# sdr_3157.net
KiCad netlist of a schematic drawn in EAGLE
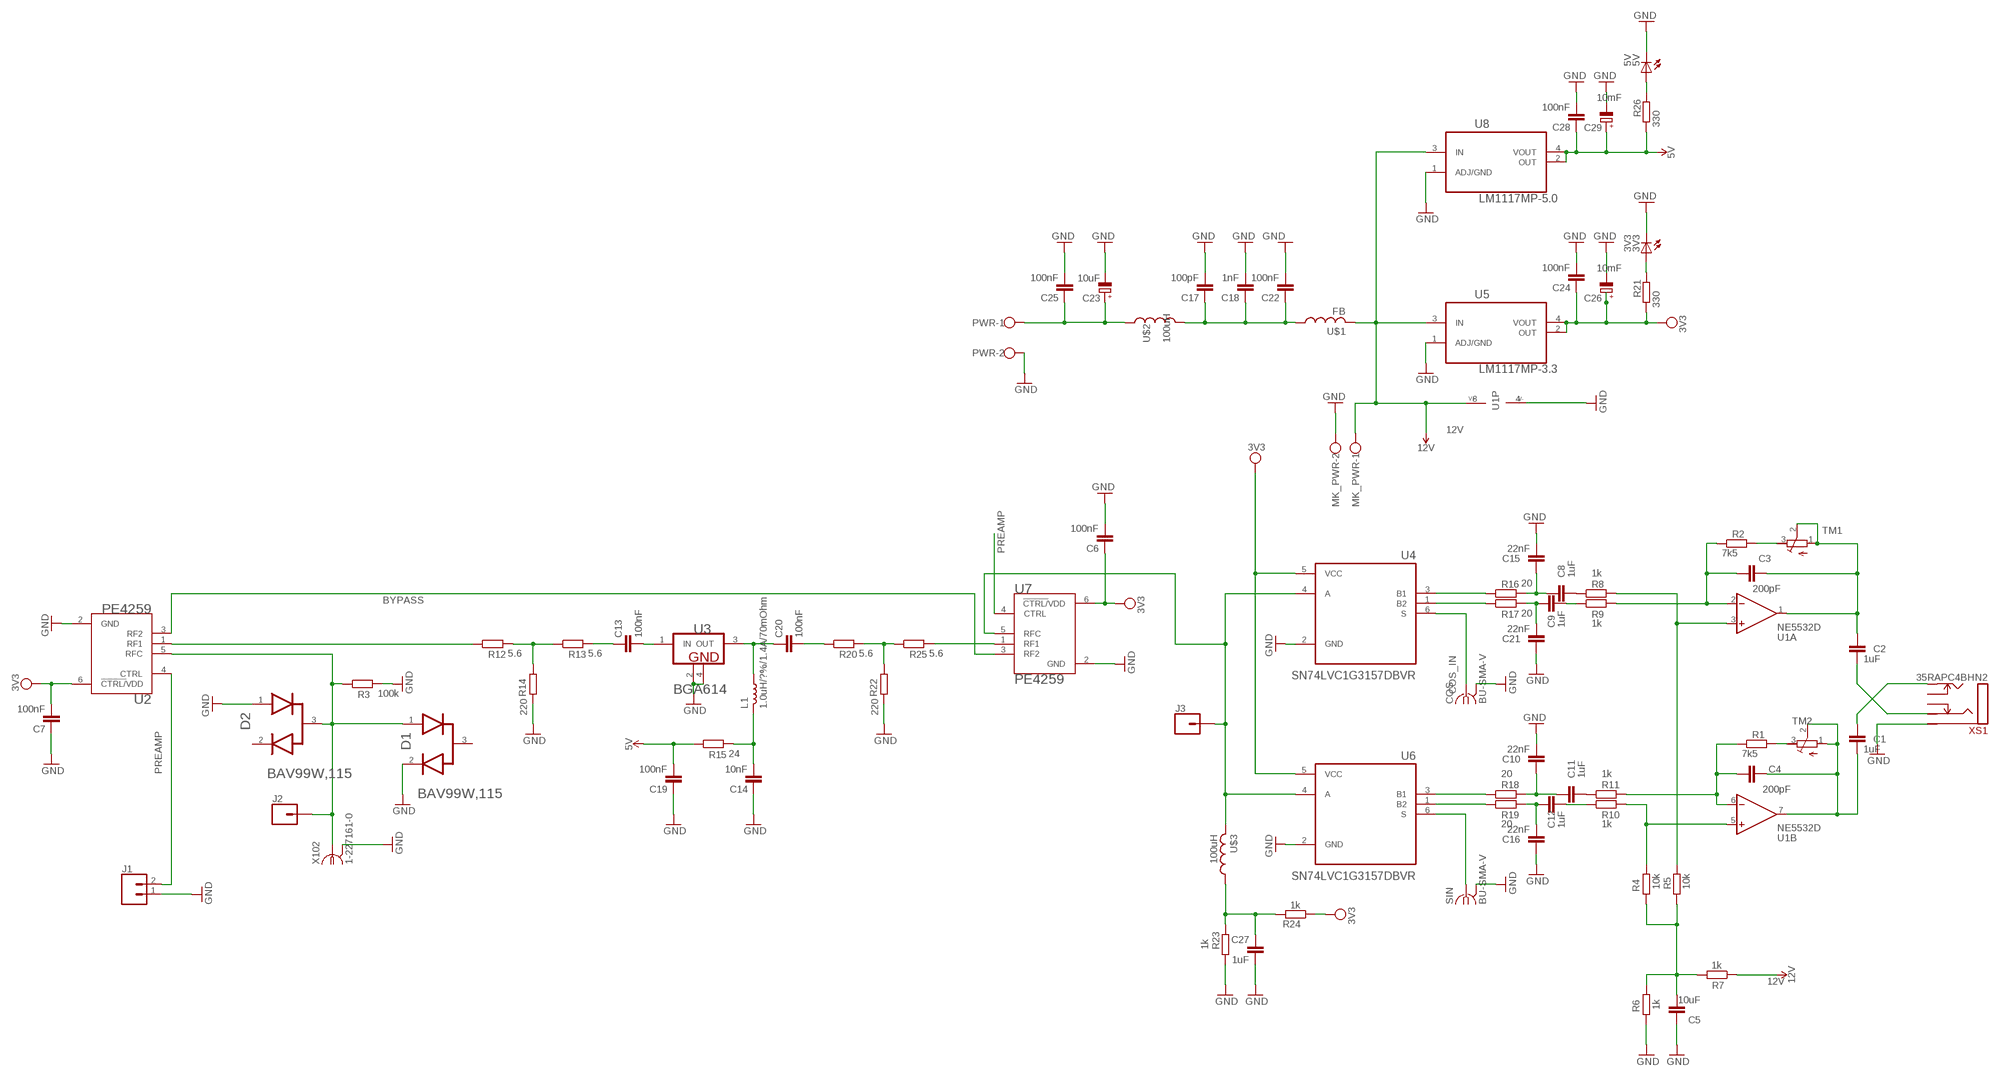
[diagram p0: schematic, sheet 1]

(export (version "E")
  (design (tool "Eeschema 10.0.6"))
  (components
    (comp (ref "3V3")
      (value "3V3")
      (footprint "eagle-import:1206")
      (libsource (lib "eagle-import") (part "LEDSMT1206"))
    )
    (comp (ref "5V")
      (value "5V")
      (footprint "eagle-import:1206")
      (libsource (lib "eagle-import") (part "LEDSMT1206"))
    )
    (comp (ref "C1")
      (value "1uF")
      (footprint "eagle-import:C050-045X075")
      (libsource (lib "eagle-import") (part "C-EU050-045X075"))
    )
    (comp (ref "C2")
      (value "1uF")
      (footprint "eagle-import:C050-045X075")
      (libsource (lib "eagle-import") (part "C-EU050-045X075"))
    )
    (comp (ref "C3")
      (value "200pF")
      (footprint "eagle-import:C050-045X075")
      (libsource (lib "eagle-import") (part "C-EU050-045X075"))
    )
    (comp (ref "C4")
      (value "200pF")
      (footprint "eagle-import:C050-045X075")
      (libsource (lib "eagle-import") (part "C-EU050-045X075"))
    )
    (comp (ref "C5")
      (value "10uF")
      (footprint "eagle-import:C0805")
      (libsource (lib "eagle-import") (part "C-EUC0805"))
    )
    (comp (ref "C6")
      (value "100nF")
      (footprint "eagle-import:C0805")
      (libsource (lib "eagle-import") (part "C-EUC0805"))
    )
    (comp (ref "C7")
      (value "100nF")
      (footprint "eagle-import:C0805")
      (libsource (lib "eagle-import") (part "C-EUC0805"))
    )
    (comp (ref "C8")
      (value "1uF")
      (footprint "eagle-import:C0805")
      (libsource (lib "eagle-import") (part "C-EUC0805"))
    )
    (comp (ref "C9")
      (value "1uF")
      (footprint "eagle-import:C0805")
      (libsource (lib "eagle-import") (part "C-EUC0805"))
    )
    (comp (ref "C10")
      (value "22nF")
      (footprint "eagle-import:C0805")
      (libsource (lib "eagle-import") (part "C-EUC0805"))
    )
    (comp (ref "C11")
      (value "1uF")
      (footprint "eagle-import:C0805")
      (libsource (lib "eagle-import") (part "C-EUC0805"))
    )
    (comp (ref "C12")
      (value "1uF")
      (footprint "eagle-import:C0805")
      (libsource (lib "eagle-import") (part "C-EUC0805"))
    )
    (comp (ref "C13")
      (value "100nF")
      (footprint "eagle-import:C0805")
      (libsource (lib "eagle-import") (part "C-EUC0805"))
    )
    (comp (ref "C14")
      (value "10nF")
      (footprint "eagle-import:C0805")
      (libsource (lib "eagle-import") (part "C-EUC0805"))
    )
    (comp (ref "C15")
      (value "22nF")
      (footprint "eagle-import:C0805")
      (libsource (lib "eagle-import") (part "C-EUC0805"))
    )
    (comp (ref "C16")
      (value "22nF")
      (footprint "eagle-import:C0805")
      (libsource (lib "eagle-import") (part "C-EUC0805"))
    )
    (comp (ref "C17")
      (value "100pF")
      (footprint "eagle-import:C0805")
      (libsource (lib "eagle-import") (part "C-EUC0805"))
    )
    (comp (ref "C18")
      (value "1nF")
      (footprint "eagle-import:C0805")
      (libsource (lib "eagle-import") (part "C-EUC0805"))
    )
    (comp (ref "C19")
      (value "100nF")
      (footprint "eagle-import:C0805")
      (libsource (lib "eagle-import") (part "C-EUC0805"))
    )
    (comp (ref "C20")
      (value "100nF")
      (footprint "eagle-import:C0805")
      (libsource (lib "eagle-import") (part "C-EUC0805"))
    )
    (comp (ref "C21")
      (value "22nF")
      (footprint "eagle-import:C0805")
      (libsource (lib "eagle-import") (part "C-EUC0805"))
    )
    (comp (ref "C22")
      (value "100nF")
      (footprint "eagle-import:C0805")
      (libsource (lib "eagle-import") (part "C-EUC0805"))
    )
    (comp (ref "C23")
      (value "10uF")
      (footprint "eagle-import:SMC_C")
      (libsource (lib "eagle-import") (part "CPOL-EUSMCC"))
    )
    (comp (ref "C24")
      (value "100nF")
      (footprint "eagle-import:C0805")
      (libsource (lib "eagle-import") (part "C-EUC0805"))
    )
    (comp (ref "C25")
      (value "100nF")
      (footprint "eagle-import:C0805")
      (libsource (lib "eagle-import") (part "C-EUC0805"))
    )
    (comp (ref "C26")
      (value "10mF")
      (footprint "eagle-import:SMC_C")
      (libsource (lib "eagle-import") (part "CPOL-EUSMCC"))
    )
    (comp (ref "C27")
      (value "1uF")
      (footprint "eagle-import:C0805")
      (libsource (lib "eagle-import") (part "C-EUC0805"))
    )
    (comp (ref "C28")
      (value "100nF")
      (footprint "eagle-import:C0805")
      (libsource (lib "eagle-import") (part "C-EUC0805"))
    )
    (comp (ref "C29")
      (value "10mF")
      (footprint "eagle-import:SMC_C")
      (libsource (lib "eagle-import") (part "CPOL-EUSMCC"))
    )
    (comp (ref "COS")
      (value "BU-SMA-V")
      (footprint "eagle-import:BU-SMA-V")
      (libsource (lib "eagle-import") (part "BU-SMA-V"))
    )
    (comp (ref "D1")
      (value "NEXPERIA_BAV99W,115NEXPERIA_BAV99W,115_0_0")
      (footprint "eagle-import:NEXPERIA_BAV99W,115_0")
      (fields
        (field (name "3DS_PART_NUMBER") "412-00001")
        (field (name "DIGIKEY_PART_NUMBER") "1727-2915-1-ND")
        (field (name "MF") "Nexperia")
      )
      (libsource (lib "eagle-import") (part "NEXPERIA_BAV99W,115NEXPERIA_BAV99W,115_0_0"))
    )
    (comp (ref "D2")
      (value "NEXPERIA_BAV99W,115NEXPERIA_BAV99W,115_0_0")
      (footprint "eagle-import:NEXPERIA_BAV99W,115_0")
      (fields
        (field (name "3DS_PART_NUMBER") "412-00001")
        (field (name "DIGIKEY_PART_NUMBER") "1727-2915-1-ND")
        (field (name "MF") "Nexperia")
      )
      (libsource (lib "eagle-import") (part "NEXPERIA_BAV99W,115NEXPERIA_BAV99W,115_0_0"))
    )
    (comp (ref "J1")
      (value "CONN_02")
      (footprint "eagle-import:1X02")
      (libsource (lib "eagle-import") (part "CONN_02"))
    )
    (comp (ref "J2")
      (value "CONN_01PTH_NO_SILK_SMALL")
      (footprint "eagle-import:1X01_SMALL")
      (libsource (lib "eagle-import") (part "CONN_01PTH_NO_SILK_SMALL"))
    )
    (comp (ref "J3")
      (value "CONN_01PTH_NO_SILK_SMALL")
      (footprint "eagle-import:1X01_SMALL")
      (libsource (lib "eagle-import") (part "CONN_01PTH_NO_SILK_SMALL"))
    )
    (comp (ref "L1")
      (value "1.0uH/?%/1.4A/70mOhm")
      (footprint "eagle-import:0805-WIDE")
      (libsource (lib "eagle-import") (part "INDUCTOR-0805_WIDE-1.0UH"))
    )
    (comp (ref "MK_PWR")
      (value "W237-102")
      (footprint "eagle-import:W237-102")
      (fields (field (name "MPN") "237-102"))
      (libsource (lib "eagle-import") (part "W237-102"))
    )
    (comp (ref "PWR")
      (value "W237-102")
      (footprint "eagle-import:W237-102")
      (fields (field (name "MPN") "237-102"))
      (libsource (lib "eagle-import") (part "W237-102"))
    )
    (comp (ref "R1")
      (value "7k5")
      (footprint "eagle-import:R0805")
      (libsource (lib "eagle-import") (part "R-EU_R0805"))
    )
    (comp (ref "R2")
      (value "7k5")
      (footprint "eagle-import:R0805")
      (libsource (lib "eagle-import") (part "R-EU_R0805"))
    )
    (comp (ref "R3")
      (value "100k")
      (footprint "eagle-import:R0805")
      (libsource (lib "eagle-import") (part "R-EU_R0805"))
    )
    (comp (ref "R4")
      (value "10k")
      (footprint "eagle-import:M0805")
      (libsource (lib "eagle-import") (part "R-EU_M0805"))
    )
    (comp (ref "R5")
      (value "10k")
      (footprint "eagle-import:R0805")
      (libsource (lib "eagle-import") (part "R-EU_R0805"))
    )
    (comp (ref "R6")
      (value "1k")
      (footprint "eagle-import:M0805")
      (libsource (lib "eagle-import") (part "R-EU_M0805"))
    )
    (comp (ref "R7")
      (value "1k")
      (footprint "eagle-import:M0805")
      (libsource (lib "eagle-import") (part "R-EU_M0805"))
    )
    (comp (ref "R8")
      (value "1k")
      (footprint "eagle-import:R0805")
      (libsource (lib "eagle-import") (part "R-EU_R0805"))
    )
    (comp (ref "R9")
      (value "1k")
      (footprint "eagle-import:R0805")
      (libsource (lib "eagle-import") (part "R-EU_R0805"))
    )
    (comp (ref "R10")
      (value "1k")
      (footprint "eagle-import:R0805")
      (libsource (lib "eagle-import") (part "R-EU_R0805"))
    )
    (comp (ref "R11")
      (value "1k")
      (footprint "eagle-import:M0805")
      (libsource (lib "eagle-import") (part "R-EU_M0805"))
    )
    (comp (ref "R12")
      (value "5.6")
      (footprint "eagle-import:R0805")
      (libsource (lib "eagle-import") (part "R-EU_R0805"))
    )
    (comp (ref "R13")
      (value "5.6")
      (footprint "eagle-import:R0805")
      (libsource (lib "eagle-import") (part "R-EU_R0805"))
    )
    (comp (ref "R14")
      (value "220")
      (footprint "eagle-import:R0805")
      (libsource (lib "eagle-import") (part "R-EU_R0805"))
    )
    (comp (ref "R15")
      (value "24")
      (footprint "eagle-import:R0805")
      (libsource (lib "eagle-import") (part "R-EU_R0805"))
    )
    (comp (ref "R16")
      (value "20")
      (footprint "eagle-import:R0805")
      (libsource (lib "eagle-import") (part "R-EU_R0805"))
    )
    (comp (ref "R17")
      (value "20")
      (footprint "eagle-import:R0805")
      (libsource (lib "eagle-import") (part "R-EU_R0805"))
    )
    (comp (ref "R18")
      (value "20")
      (footprint "eagle-import:R0805")
      (libsource (lib "eagle-import") (part "R-EU_R0805"))
    )
    (comp (ref "R19")
      (value "20")
      (footprint "eagle-import:R0805")
      (libsource (lib "eagle-import") (part "R-EU_R0805"))
    )
    (comp (ref "R20")
      (value "5.6")
      (footprint "eagle-import:R0805")
      (libsource (lib "eagle-import") (part "R-EU_R0805"))
    )
    (comp (ref "R21")
      (value "330")
      (footprint "eagle-import:R0805")
      (libsource (lib "eagle-import") (part "R-EU_R0805"))
    )
    (comp (ref "R22")
      (value "220")
      (footprint "eagle-import:R0805")
      (libsource (lib "eagle-import") (part "R-EU_R0805"))
    )
    (comp (ref "R23")
      (value "1k")
      (footprint "eagle-import:R0805")
      (libsource (lib "eagle-import") (part "R-EU_R0805"))
    )
    (comp (ref "R24")
      (value "1k")
      (footprint "eagle-import:R0805")
      (libsource (lib "eagle-import") (part "R-EU_R0805"))
    )
    (comp (ref "R25")
      (value "5.6")
      (footprint "eagle-import:R0805")
      (libsource (lib "eagle-import") (part "R-EU_R0805"))
    )
    (comp (ref "R26")
      (value "330")
      (footprint "eagle-import:R0805")
      (libsource (lib "eagle-import") (part "R-EU_R0805"))
    )
    (comp (ref "SIN")
      (value "BU-SMA-V")
      (footprint "eagle-import:BU-SMA-V")
      (libsource (lib "eagle-import") (part "BU-SMA-V"))
    )
    (comp (ref "TM1")
      (value "5k")
      (footprint "eagle-import:RTRIM3296W")
      (libsource (lib "eagle-import") (part "R-TRIMM3296W"))
    )
    (comp (ref "TM2")
      (value "5k")
      (footprint "eagle-import:RTRIM3296W")
      (libsource (lib "eagle-import") (part "R-TRIMM3296W"))
    )
    (comp (ref "U$1") (value "FB") (footprint "eagle-import:FB") (libsource (lib "eagle-import") (part "FB")))
    (comp (ref "U$2")
      (value "100uH")
      (footprint "eagle-import:IHLP4040")
      (libsource (lib "eagle-import") (part "IHLP4040"))
    )
    (comp (ref "U$3")
      (value "100uH")
      (footprint "eagle-import:LQH55")
      (libsource (lib "eagle-import") (part "L-LQH55"))
    )
    (comp (ref "U1")
      (value "NE5532D")
      (footprint "eagle-import:SO08")
      (libsource (lib "eagle-import") (part "NE5532D"))
    )
    (comp (ref "U2")
      (value "PE4259")
      (footprint "eagle-import:SOT65P215X110-6N")
      (fields (field (name "MF") "pSemi"))
      (libsource (lib "eagle-import") (part "PE4259"))
    )
    (comp (ref "U3")
      (value "INFINEON_BGA614INFINEON_BGA614_0_0")
      (footprint "eagle-import:INFINEON_BGA614_0")
      (fields (field (name "MF") "Infineon") (field (name "MPN") "BGA614"))
      (libsource (lib "eagle-import") (part "INFINEON_BGA614INFINEON_BGA614_0_0"))
    )
    (comp (ref "U4")
      (value "SN74LVC1G3157DBVR")
      (footprint "eagle-import:SOT95P280X145-6N")
      (fields (field (name "MF") "Texas Instruments"))
      (libsource (lib "eagle-import") (part "SN74LVC1G3157DBVR"))
    )
    (comp (ref "U5")
      (value "LM1117MP-3.3")
      (footprint "eagle-import:SOT230P696X180-4N")
      (fields (field (name "MF") "Texas Instruments"))
      (libsource (lib "eagle-import") (part "LM1117MP-3.3"))
    )
    (comp (ref "U6")
      (value "SN74LVC1G3157DBVR")
      (footprint "eagle-import:SOT95P280X145-6N")
      (fields (field (name "MF") "Texas Instruments"))
      (libsource (lib "eagle-import") (part "SN74LVC1G3157DBVR"))
    )
    (comp (ref "U7")
      (value "PE4259")
      (footprint "eagle-import:SOT65P215X110-6N")
      (fields (field (name "MF") "pSemi"))
      (libsource (lib "eagle-import") (part "PE4259"))
    )
    (comp (ref "U8")
      (value "LM1117MP-5.0")
      (footprint "eagle-import:SOT230P696X180-4N")
      (fields (field (name "MF") "Texas Instruments") (field (name "MP") "LM1117MP-3.3"))
      (libsource (lib "eagle-import") (part "LM1117MP-3.3"))
    )
    (comp (ref "X102")
      (value "1-227161-0")
      (footprint "eagle-import:AMP_227161")
      (fields (field (name "MF") "TYCO ELECTRONICS") (field (name "MPN") "1-227161"))
      (libsource (lib "eagle-import") (part "?2271611--0"))
    )
    (comp (ref "XS1")
      (value "35RAPC4BHN2")
      (footprint "eagle-import:35RAP")
      (libsource (lib "eagle-import") (part "35RAPC4BHN2"))
    )
  )
  (nets
    (net (code "1") (name "/BYPASS") (class "Default")
      (node (ref "U2") (pin "3") (pinfunction "RF2_3") (pintype "passive"))
      (node (ref "U7") (pin "3") (pinfunction "RF2_3") (pintype "passive"))
    )
    (net (code "2") (name "/COS_IN") (class "Default")
      (node (ref "COS") (pin "1") (pinfunction "1_1") (pintype "passive"))
      (node (ref "U4") (pin "6") (pinfunction "S_6") (pintype "input"))
    )
    (net (code "3") (name "/PREAMP") (class "Default")
      (node (ref "J1") (pin "2") (pinfunction "2_2") (pintype "passive"))
      (node (ref "U2") (pin "4") (pinfunction "CTRL_4") (pintype "input"))
      (node (ref "U7") (pin "4") (pinfunction "CTRL_4") (pintype "input"))
    )
    (net (code "4") (name "3V3") (class "Default")
      (node (ref "C24") (pin "1") (pinfunction "1_1") (pintype "passive"))
      (node (ref "C26") (pin "+") (pinfunction "+_+") (pintype "passive"))
      (node (ref "C6") (pin "1") (pinfunction "1_1") (pintype "passive"))
      (node (ref "C7") (pin "2") (pinfunction "2_2") (pintype "passive"))
      (node (ref "R21") (pin "1") (pinfunction "1_1") (pintype "passive"))
      (node (ref "R24") (pin "1") (pinfunction "1_1") (pintype "passive"))
      (node (ref "U2") (pin "6") (pinfunction "~{CTRL/}VDD_6") (pintype "power_in"))
      (node (ref "U4") (pin "5") (pinfunction "VCC_5") (pintype "power_in"))
      (node (ref "U5") (pin "2") (pinfunction "OUT_2") (pintype "output"))
      (node (ref "U5") (pin "4") (pinfunction "VOUT_4") (pintype "output"))
      (node (ref "U6") (pin "5") (pinfunction "VCC_5") (pintype "power_in"))
      (node (ref "U7") (pin "6") (pinfunction "~{CTRL/}VDD_6") (pintype "power_in"))
    )
    (net (code "5") (name "5V") (class "Default")
      (node (ref "C19") (pin "2") (pinfunction "2_2") (pintype "passive"))
      (node (ref "C28") (pin "1") (pinfunction "1_1") (pintype "passive"))
      (node (ref "C29") (pin "+") (pinfunction "+_+") (pintype "passive"))
      (node (ref "R15") (pin "1") (pinfunction "1_1") (pintype "passive"))
      (node (ref "R26") (pin "1") (pinfunction "1_1") (pintype "passive"))
      (node (ref "U8") (pin "2") (pinfunction "OUT_2") (pintype "output"))
      (node (ref "U8") (pin "4") (pinfunction "VOUT_4") (pintype "output"))
    )
    (net (code "6") (name "12V") (class "Default")
      (node (ref "MK_PWR") (pin "1") (pinfunction "KL_1") (pintype "passive"))
      (node (ref "R7") (pin "1") (pinfunction "1_1") (pintype "passive"))
      (node (ref "U$1") (pin "P$2") (pinfunction "2_P$2") (pintype "passive"))
      (node (ref "U1") (pin "8") (pinfunction "V+_8") (pintype "power_in"))
      (node (ref "U5") (pin "3") (pinfunction "IN_3") (pintype "input"))
      (node (ref "U8") (pin "3") (pinfunction "IN_3") (pintype "input"))
    )
    (net (code "7") (name "GND") (class "Default")
      (node (ref "3V3") (pin "C") (pinfunction "C_C") (pintype "passive"))
      (node (ref "5V") (pin "C") (pinfunction "C_C") (pintype "passive"))
      (node (ref "C10") (pin "2") (pinfunction "2_2") (pintype "passive"))
      (node (ref "C14") (pin "1") (pinfunction "1_1") (pintype "passive"))
      (node (ref "C15") (pin "2") (pinfunction "2_2") (pintype "passive"))
      (node (ref "C16") (pin "1") (pinfunction "1_1") (pintype "passive"))
      (node (ref "C17") (pin "2") (pinfunction "2_2") (pintype "passive"))
      (node (ref "C18") (pin "2") (pinfunction "2_2") (pintype "passive"))
      (node (ref "C19") (pin "1") (pinfunction "1_1") (pintype "passive"))
      (node (ref "C21") (pin "1") (pinfunction "1_1") (pintype "passive"))
      (node (ref "C22") (pin "2") (pinfunction "2_2") (pintype "passive"))
      (node (ref "C23") (pin "-") (pinfunction "-_-") (pintype "passive"))
      (node (ref "C24") (pin "2") (pinfunction "2_2") (pintype "passive"))
      (node (ref "C25") (pin "2") (pinfunction "2_2") (pintype "passive"))
      (node (ref "C26") (pin "-") (pinfunction "-_-") (pintype "passive"))
      (node (ref "C27") (pin "1") (pinfunction "1_1") (pintype "passive"))
      (node (ref "C28") (pin "2") (pinfunction "2_2") (pintype "passive"))
      (node (ref "C29") (pin "-") (pinfunction "-_-") (pintype "passive"))
      (node (ref "C5") (pin "1") (pinfunction "1_1") (pintype "passive"))
      (node (ref "C6") (pin "2") (pinfunction "2_2") (pintype "passive"))
      (node (ref "C7") (pin "1") (pinfunction "1_1") (pintype "passive"))
      (node (ref "COS") (pin "2") (pinfunction "2_2") (pintype "passive"))
      (node (ref "COS") (pin "3") (pinfunction "2_3") (pintype "passive"))
      (node (ref "COS") (pin "4") (pinfunction "2_4") (pintype "passive"))
      (node (ref "COS") (pin "5") (pinfunction "2_5") (pintype "passive"))
      (node (ref "D1") (pin "2") (pinfunction "2_CATHODE_2") (pintype "passive"))
      (node (ref "D2") (pin "1") (pinfunction "1_ANODE_1") (pintype "passive"))
      (node (ref "J1") (pin "1") (pinfunction "1_1") (pintype "passive"))
      (node (ref "MK_PWR") (pin "2") (pinfunction "KL_2") (pintype "passive"))
      (node (ref "PWR") (pin "2") (pinfunction "KL_2") (pintype "passive"))
      (node (ref "R14") (pin "2") (pinfunction "2_2") (pintype "passive"))
      (node (ref "R22") (pin "2") (pinfunction "2_2") (pintype "passive"))
      (node (ref "R23") (pin "1") (pinfunction "1_1") (pintype "passive"))
      (node (ref "R3") (pin "2") (pinfunction "2_2") (pintype "passive"))
      (node (ref "R6") (pin "1") (pinfunction "1_1") (pintype "passive"))
      (node (ref "SIN") (pin "2") (pinfunction "2_2") (pintype "passive"))
      (node (ref "SIN") (pin "3") (pinfunction "2_3") (pintype "passive"))
      (node (ref "SIN") (pin "4") (pinfunction "2_4") (pintype "passive"))
      (node (ref "SIN") (pin "5") (pinfunction "2_5") (pintype "passive"))
      (node (ref "U1") (pin "4") (pinfunction "V-_4") (pintype "power_in"))
      (node (ref "U2") (pin "2") (pinfunction "GND_2") (pintype "power_in"))
      (node (ref "U3") (pin "2") (pinfunction "1_GND_2") (pintype "power_in"))
      (node (ref "U3") (pin "4") (pinfunction "2_GND_4") (pintype "power_in"))
      (node (ref "U4") (pin "2") (pinfunction "GND_2") (pintype "power_in"))
      (node (ref "U5") (pin "1") (pinfunction "ADJ/GND_1") (pintype "passive"))
      (node (ref "U6") (pin "2") (pinfunction "GND_2") (pintype "power_in"))
      (node (ref "U7") (pin "2") (pinfunction "GND_2") (pintype "power_in"))
      (node (ref "U8") (pin "1") (pinfunction "ADJ/GND_1") (pintype "passive"))
      (node (ref "X102") (pin "2") (pinfunction "2_2") (pintype "passive"))
      (node (ref "XS1") (pin "1") (pinfunction "S_1") (pintype "passive"))
    )
    (net (code "8") (name "Net-(3V3-PadA)") (class "Default")
      (node (ref "3V3") (pin "A") (pinfunction "A_A") (pintype "passive"))
      (node (ref "R21") (pin "2") (pinfunction "2_2") (pintype "passive"))
    )
    (net (code "9") (name "Net-(5V-PadA)") (class "Default")
      (node (ref "5V") (pin "A") (pinfunction "A_A") (pintype "passive"))
      (node (ref "R26") (pin "2") (pinfunction "2_2") (pintype "passive"))
    )
    (net (code "10") (name "Net-(C5-Pad2)") (class "Default")
      (node (ref "C5") (pin "2") (pinfunction "2_2") (pintype "passive"))
      (node (ref "R4") (pin "1") (pinfunction "1_1") (pintype "passive"))
      (node (ref "R5") (pin "1") (pinfunction "1_1") (pintype "passive"))
      (node (ref "R6") (pin "2") (pinfunction "2_2") (pintype "passive"))
      (node (ref "R7") (pin "2") (pinfunction "2_2") (pintype "passive"))
    )
    (net (code "11") (name "Net-(C8-Pad2)") (class "Default")
      (node (ref "C8") (pin "2") (pinfunction "2_2") (pintype "passive"))
      (node (ref "R8") (pin "1") (pinfunction "1_1") (pintype "passive"))
    )
    (net (code "12") (name "Net-(C9-Pad2)") (class "Default")
      (node (ref "C9") (pin "2") (pinfunction "2_2") (pintype "passive"))
      (node (ref "R9") (pin "1") (pinfunction "1_1") (pintype "passive"))
    )
    (net (code "13") (name "Net-(C10-Pad1)") (class "Default")
      (node (ref "C10") (pin "1") (pinfunction "1_1") (pintype "passive"))
      (node (ref "C11") (pin "1") (pinfunction "1_1") (pintype "passive"))
      (node (ref "R18") (pin "2") (pinfunction "2_2") (pintype "passive"))
    )
    (net (code "14") (name "Net-(C11-Pad2)") (class "Default")
      (node (ref "C11") (pin "2") (pinfunction "2_2") (pintype "passive"))
      (node (ref "R11") (pin "1") (pinfunction "1_1") (pintype "passive"))
    )
    (net (code "15") (name "Net-(C12-Pad1)") (class "Default")
      (node (ref "C12") (pin "1") (pinfunction "1_1") (pintype "passive"))
      (node (ref "C16") (pin "2") (pinfunction "2_2") (pintype "passive"))
      (node (ref "R19") (pin "2") (pinfunction "2_2") (pintype "passive"))
    )
    (net (code "16") (name "Net-(C12-Pad2)") (class "Default")
      (node (ref "C12") (pin "2") (pinfunction "2_2") (pintype "passive"))
      (node (ref "R10") (pin "1") (pinfunction "1_1") (pintype "passive"))
    )
    (net (code "17") (name "Net-(C13-Pad1)") (class "Default")
      (node (ref "C13") (pin "1") (pinfunction "1_1") (pintype "passive"))
      (node (ref "R13") (pin "2") (pinfunction "2_2") (pintype "passive"))
    )
    (net (code "18") (name "Net-(C14-Pad2)") (class "Default")
      (node (ref "C14") (pin "2") (pinfunction "2_2") (pintype "passive"))
      (node (ref "L1") (pin "2") (pinfunction "2_2") (pintype "passive"))
      (node (ref "R15") (pin "2") (pinfunction "2_2") (pintype "passive"))
    )
    (net (code "19") (name "Net-(C15-Pad1)") (class "Default")
      (node (ref "C15") (pin "1") (pinfunction "1_1") (pintype "passive"))
      (node (ref "C8") (pin "1") (pinfunction "1_1") (pintype "passive"))
      (node (ref "R16") (pin "2") (pinfunction "2_2") (pintype "passive"))
    )
    (net (code "20") (name "Net-(C20-Pad2)") (class "Default")
      (node (ref "C20") (pin "2") (pinfunction "2_2") (pintype "passive"))
      (node (ref "R20") (pin "1") (pinfunction "1_1") (pintype "passive"))
    )
    (net (code "21") (name "Net-(C21-Pad2)") (class "Default")
      (node (ref "C21") (pin "2") (pinfunction "2_2") (pintype "passive"))
      (node (ref "C9") (pin "1") (pinfunction "1_1") (pintype "passive"))
      (node (ref "R17") (pin "2") (pinfunction "2_2") (pintype "passive"))
    )
    (net (code "22") (name "Net-(C27-Pad2)") (class "Default")
      (node (ref "C27") (pin "2") (pinfunction "2_2") (pintype "passive"))
      (node (ref "R23") (pin "2") (pinfunction "2_2") (pintype "passive"))
      (node (ref "R24") (pin "2") (pinfunction "2_2") (pintype "passive"))
      (node (ref "U$3") (pin "1") (pinfunction "1_1") (pintype "passive"))
    )
    (net (code "23") (name "Net-(D1-1_ANODE)") (class "Default")
      (node (ref "D1") (pin "1") (pinfunction "1_ANODE_1") (pintype "passive"))
      (node (ref "D2") (pin "3") (pinfunction "1_CATHODE/2_ANODE_3") (pintype "passive"))
      (node (ref "J2") (pin "P$1") (pinfunction "1_P$1") (pintype "passive"))
      (node (ref "R3") (pin "1") (pinfunction "1_1") (pintype "passive"))
      (node (ref "U2") (pin "5") (pinfunction "RFC_5") (pintype "passive"))
      (node (ref "X102") (pin "1") (pinfunction "1_1") (pintype "passive"))
    )
    (net (code "24") (name "Net-(J3-1)") (class "Default")
      (node (ref "J3") (pin "P$1") (pinfunction "1_P$1") (pintype "passive"))
      (node (ref "U$3") (pin "2") (pinfunction "2_2") (pintype "passive"))
      (node (ref "U4") (pin "4") (pinfunction "A_4") (pintype "output"))
      (node (ref "U6") (pin "4") (pinfunction "A_4") (pintype "output"))
      (node (ref "U7") (pin "5") (pinfunction "RFC_5") (pintype "passive"))
    )
    (net (code "25") (name "Net-(PWRA-KL)") (class "Default")
      (node (ref "C23") (pin "+") (pinfunction "+_+") (pintype "passive"))
      (node (ref "C25") (pin "1") (pinfunction "1_1") (pintype "passive"))
      (node (ref "PWR") (pin "1") (pinfunction "KL_1") (pintype "passive"))
      (node (ref "U$2") (pin "1") (pinfunction "1_1") (pintype "passive"))
    )
    (net (code "26") (name "Net-(R12-Pad2)") (class "Default")
      (node (ref "R12") (pin "2") (pinfunction "2_2") (pintype "passive"))
      (node (ref "R13") (pin "1") (pinfunction "1_1") (pintype "passive"))
      (node (ref "R14") (pin "1") (pinfunction "1_1") (pintype "passive"))
    )
    (net (code "27") (name "Net-(R20-Pad2)") (class "Default")
      (node (ref "R20") (pin "2") (pinfunction "2_2") (pintype "passive"))
      (node (ref "R22") (pin "1") (pinfunction "1_1") (pintype "passive"))
      (node (ref "R25") (pin "1") (pinfunction "1_1") (pintype "passive"))
    )
    (net (code "28") (name "Net-(TM1-A)") (class "Default")
      (node (ref "C2") (pin "1") (pinfunction "1_1") (pintype "passive"))
      (node (ref "C3") (pin "2") (pinfunction "2_2") (pintype "passive"))
      (node (ref "TM1") (pin "1") (pinfunction "A_1") (pintype "passive"))
      (node (ref "TM1") (pin "2") (pinfunction "S_2") (pintype "passive"))
      (node (ref "U1") (pin "1") (pinfunction "OUT_1") (pintype "output"))
    )
    (net (code "29") (name "Net-(TM1-E)") (class "Default")
      (node (ref "R2") (pin "2") (pinfunction "2_2") (pintype "passive"))
      (node (ref "TM1") (pin "3") (pinfunction "E_3") (pintype "passive"))
    )
    (net (code "30") (name "Net-(TM2-A)") (class "Default")
      (node (ref "C1") (pin "2") (pinfunction "2_2") (pintype "passive"))
      (node (ref "C4") (pin "2") (pinfunction "2_2") (pintype "passive"))
      (node (ref "TM2") (pin "1") (pinfunction "A_1") (pintype "passive"))
      (node (ref "TM2") (pin "2") (pinfunction "S_2") (pintype "passive"))
      (node (ref "U1") (pin "7") (pinfunction "OUT_7") (pintype "output"))
    )
    (net (code "31") (name "Net-(TM2-E)") (class "Default")
      (node (ref "R1") (pin "2") (pinfunction "2_2") (pintype "passive"))
      (node (ref "TM2") (pin "3") (pinfunction "E_3") (pintype "passive"))
    )
    (net (code "32") (name "Net-(U$1-1)") (class "Default")
      (node (ref "C17") (pin "1") (pinfunction "1_1") (pintype "passive"))
      (node (ref "C18") (pin "1") (pinfunction "1_1") (pintype "passive"))
      (node (ref "C22") (pin "1") (pinfunction "1_1") (pintype "passive"))
      (node (ref "U$1") (pin "P$1") (pinfunction "1_P$1") (pintype "passive"))
      (node (ref "U$2") (pin "2") (pinfunction "2_2") (pintype "passive"))
    )
    (net (code "33") (name "Net-(U1A-+IN)") (class "Default")
      (node (ref "R5") (pin "2") (pinfunction "2_2") (pintype "passive"))
      (node (ref "R8") (pin "2") (pinfunction "2_2") (pintype "passive"))
      (node (ref "U1") (pin "3") (pinfunction "+IN_3") (pintype "input"))
    )
    (net (code "34") (name "Net-(U1A--IN)") (class "Default")
      (node (ref "C3") (pin "1") (pinfunction "1_1") (pintype "passive"))
      (node (ref "R2") (pin "1") (pinfunction "1_1") (pintype "passive"))
      (node (ref "R9") (pin "2") (pinfunction "2_2") (pintype "passive"))
      (node (ref "U1") (pin "2") (pinfunction "-IN_2") (pintype "input"))
    )
    (net (code "35") (name "Net-(U1B-+IN)") (class "Default")
      (node (ref "R10") (pin "2") (pinfunction "2_2") (pintype "passive"))
      (node (ref "R4") (pin "2") (pinfunction "2_2") (pintype "passive"))
      (node (ref "U1") (pin "5") (pinfunction "+IN_5") (pintype "input"))
    )
    (net (code "36") (name "Net-(U1B--IN)") (class "Default")
      (node (ref "C4") (pin "1") (pinfunction "1_1") (pintype "passive"))
      (node (ref "R1") (pin "1") (pinfunction "1_1") (pintype "passive"))
      (node (ref "R11") (pin "2") (pinfunction "2_2") (pintype "passive"))
      (node (ref "U1") (pin "6") (pinfunction "-IN_6") (pintype "input"))
    )
    (net (code "37") (name "Net-(U2-RF1)") (class "Default")
      (node (ref "R12") (pin "1") (pinfunction "1_1") (pintype "passive"))
      (node (ref "U2") (pin "1") (pinfunction "RF1_1") (pintype "passive"))
    )
    (net (code "38") (name "Net-(U3-IN)") (class "Default")
      (node (ref "C13") (pin "2") (pinfunction "2_2") (pintype "passive"))
      (node (ref "U3") (pin "1") (pinfunction "IN_1") (pintype "input"))
    )
    (net (code "39") (name "Net-(U3-OUT)") (class "Default")
      (node (ref "C20") (pin "1") (pinfunction "1_1") (pintype "passive"))
      (node (ref "L1") (pin "1") (pinfunction "1_1") (pintype "passive"))
      (node (ref "U3") (pin "3") (pinfunction "OUT_3") (pintype "output"))
    )
    (net (code "40") (name "Net-(U4-B1)") (class "Default")
      (node (ref "R16") (pin "1") (pinfunction "1_1") (pintype "passive"))
      (node (ref "U4") (pin "3") (pinfunction "B1_3") (pintype "input"))
    )
    (net (code "41") (name "Net-(U4-B2)") (class "Default")
      (node (ref "R17") (pin "1") (pinfunction "1_1") (pintype "passive"))
      (node (ref "U4") (pin "1") (pinfunction "B2_1") (pintype "input"))
    )
    (net (code "42") (name "Net-(U6-B1)") (class "Default")
      (node (ref "R18") (pin "1") (pinfunction "1_1") (pintype "passive"))
      (node (ref "U6") (pin "3") (pinfunction "B1_3") (pintype "input"))
    )
    (net (code "43") (name "Net-(U6-B2)") (class "Default")
      (node (ref "R19") (pin "1") (pinfunction "1_1") (pintype "passive"))
      (node (ref "U6") (pin "1") (pinfunction "B2_1") (pintype "input"))
    )
    (net (code "44") (name "Net-(U6-S)") (class "Default")
      (node (ref "SIN") (pin "1") (pinfunction "1_1") (pintype "passive"))
      (node (ref "U6") (pin "6") (pinfunction "S_6") (pintype "input"))
    )
    (net (code "45") (name "Net-(U7-RF1)") (class "Default")
      (node (ref "R25") (pin "2") (pinfunction "2_2") (pintype "passive"))
      (node (ref "U7") (pin "1") (pinfunction "RF1_1") (pintype "passive"))
    )
    (net (code "46") (name "Net-(XS1-R)") (class "Default")
      (node (ref "C2") (pin "2") (pinfunction "2_2") (pintype "passive"))
      (node (ref "XS1") (pin "3") (pinfunction "R_3") (pintype "passive"))
    )
    (net (code "47") (name "Net-(XS1-T)") (class "Default")
      (node (ref "C1") (pin "1") (pinfunction "1_1") (pintype "passive"))
      (node (ref "XS1") (pin "2") (pinfunction "T_2") (pintype "passive"))
    )
    (net (code "48") (name "unconnected-(D1-1_CATHODE{slash}2_ANODE-Pad3)") (class "Default")
      (node (ref "D1") (pin "3") (pinfunction "1_CATHODE/2_ANODE_3") (pintype "passive"))
    )
    (net (code "49") (name "unconnected-(D2-2_CATHODE-Pad2)") (class "Default")
      (node (ref "D2") (pin "2") (pinfunction "2_CATHODE_2") (pintype "passive"))
    )
    (net (code "50") (name "unconnected-(XS1-RN-Pad11)") (class "Default")
      (node (ref "XS1") (pin "11") (pinfunction "RN_11") (pintype "passive"))
    )
    (net (code "51") (name "unconnected-(XS1-TN-Pad10)") (class "Default")
      (node (ref "XS1") (pin "10") (pinfunction "TN_10") (pintype "passive"))
    )
  )
)
